# motor-control.net
KiCad netlist of a schematic drawn in EAGLE
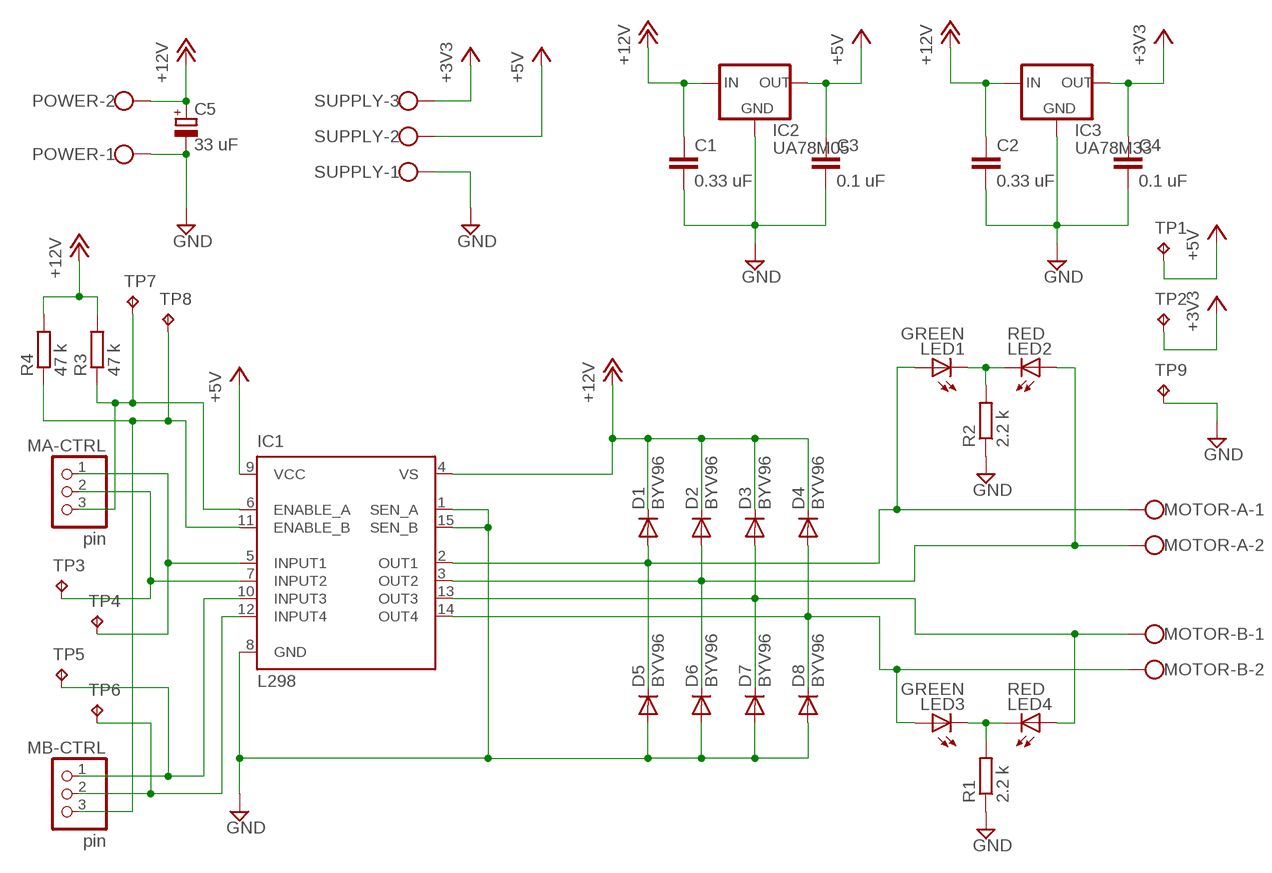
[diagram p0: schematic, sheet 1]

(export (version "E")
  (design (tool "Eeschema 10.0.6"))
  (components
    (comp (ref "C1")
      (value "0.33 uF")
      (footprint "eagle-import:C050-024X044")
      (libsource (lib "eagle-import") (part "C-EU050-024X044"))
    )
    (comp (ref "C2")
      (value "0.33 uF")
      (footprint "eagle-import:C050-024X044")
      (libsource (lib "eagle-import") (part "C-EU050-024X044"))
    )
    (comp (ref "C3")
      (value "0.1 uF")
      (footprint "eagle-import:C050-024X044")
      (libsource (lib "eagle-import") (part "C-EU050-024X044"))
    )
    (comp (ref "C4")
      (value "0.1 uF")
      (footprint "eagle-import:C050-024X044")
      (libsource (lib "eagle-import") (part "C-EU050-024X044"))
    )
    (comp (ref "C5")
      (value "33 uF")
      (footprint "eagle-import:E2,5-5")
      (libsource (lib "eagle-import") (part "CPOL-EUE2.5-5"))
    )
    (comp (ref "D1")
      (value "BYV96")
      (footprint "eagle-import:SOD57-10")
      (libsource (lib "eagle-import") (part "BYV96"))
    )
    (comp (ref "D2")
      (value "BYV96")
      (footprint "eagle-import:SOD57-10")
      (libsource (lib "eagle-import") (part "BYV96"))
    )
    (comp (ref "D3")
      (value "BYV96")
      (footprint "eagle-import:SOD57-10")
      (libsource (lib "eagle-import") (part "BYV96"))
    )
    (comp (ref "D4")
      (value "BYV96")
      (footprint "eagle-import:SOD57-10")
      (libsource (lib "eagle-import") (part "BYV96"))
    )
    (comp (ref "D5")
      (value "BYV96")
      (footprint "eagle-import:SOD57-10")
      (libsource (lib "eagle-import") (part "BYV96"))
    )
    (comp (ref "D6")
      (value "BYV96")
      (footprint "eagle-import:SOD57-10")
      (libsource (lib "eagle-import") (part "BYV96"))
    )
    (comp (ref "D7")
      (value "BYV96")
      (footprint "eagle-import:SOD57-10")
      (libsource (lib "eagle-import") (part "BYV96"))
    )
    (comp (ref "D8")
      (value "BYV96")
      (footprint "eagle-import:SOD57-10")
      (libsource (lib "eagle-import") (part "BYV96"))
    )
    (comp (ref "IC1")
      (value "L298")
      (footprint "eagle-import:MULTIWATT-15")
      (libsource (lib "eagle-import") (part "L298"))
    )
    (comp (ref "IC2")
      (value "UA78M05")
      (footprint "eagle-import:78XXS")
      (libsource (lib "eagle-import") (part "78XXS"))
    )
    (comp (ref "IC3")
      (value "UA78M33")
      (footprint "eagle-import:78XXS")
      (libsource (lib "eagle-import") (part "78XXS"))
    )
    (comp (ref "LED1")
      (value "GREEN")
      (footprint "eagle-import:LED5MM")
      (libsource (lib "eagle-import") (part "LED5MM"))
    )
    (comp (ref "LED2")
      (value "RED")
      (footprint "eagle-import:LED5MM")
      (libsource (lib "eagle-import") (part "LED5MM"))
    )
    (comp (ref "LED3")
      (value "GREEN")
      (footprint "eagle-import:LED5MM")
      (libsource (lib "eagle-import") (part "LED5MM"))
    )
    (comp (ref "LED4")
      (value "RED")
      (footprint "eagle-import:LED5MM")
      (libsource (lib "eagle-import") (part "LED5MM"))
    )
    (comp (ref "MA-CTRL")
      (value "pin")
      (footprint "eagle-import:1X03")
      (libsource (lib "eagle-import") (part "PINHD-1X3"))
    )
    (comp (ref "MB-CTRL")
      (value "pin")
      (footprint "eagle-import:1X03")
      (libsource (lib "eagle-import") (part "PINHD-1X3"))
    )
    (comp (ref "MOTOR-A")
      (value "W237-02P")
      (footprint "eagle-import:W237-132")
      (libsource (lib "eagle-import") (part "W237-02P"))
    )
    (comp (ref "MOTOR-B")
      (value "W237-02P")
      (footprint "eagle-import:W237-132")
      (libsource (lib "eagle-import") (part "W237-02P"))
    )
    (comp (ref "POWER")
      (value "W237-02P")
      (footprint "eagle-import:W237-132")
      (libsource (lib "eagle-import") (part "W237-02P"))
    )
    (comp (ref "R1")
      (value "2.2 k")
      (footprint "eagle-import:0207_7")
      (libsource (lib "eagle-import") (part "R-EU_0207/7"))
    )
    (comp (ref "R2")
      (value "2.2 k")
      (footprint "eagle-import:0207_7")
      (libsource (lib "eagle-import") (part "R-EU_0207/7"))
    )
    (comp (ref "R3")
      (value "47 k")
      (footprint "eagle-import:0207_7")
      (libsource (lib "eagle-import") (part "R-EU_0207/7"))
    )
    (comp (ref "R4")
      (value "47 k")
      (footprint "eagle-import:0207_7")
      (libsource (lib "eagle-import") (part "R-EU_0207/7"))
    )
    (comp (ref "SUPPLY")
      (value "W237-03P")
      (footprint "eagle-import:W237-133")
      (libsource (lib "eagle-import") (part "W237-03P"))
    )
    (comp (ref "TP1")
      (value "TPTP14SQ")
      (footprint "eagle-import:TP14SQ")
      (libsource (lib "eagle-import") (part "TPTP14SQ"))
    )
    (comp (ref "TP2")
      (value "TPTP14SQ")
      (footprint "eagle-import:TP14SQ")
      (libsource (lib "eagle-import") (part "TPTP14SQ"))
    )
    (comp (ref "TP3")
      (value "TPTP14SQ")
      (footprint "eagle-import:TP14SQ")
      (libsource (lib "eagle-import") (part "TPTP14SQ"))
    )
    (comp (ref "TP4")
      (value "TPTP14SQ")
      (footprint "eagle-import:TP14SQ")
      (libsource (lib "eagle-import") (part "TPTP14SQ"))
    )
    (comp (ref "TP5")
      (value "TPTP14SQ")
      (footprint "eagle-import:TP14SQ")
      (libsource (lib "eagle-import") (part "TPTP14SQ"))
    )
    (comp (ref "TP6")
      (value "TPTP14SQ")
      (footprint "eagle-import:TP14SQ")
      (libsource (lib "eagle-import") (part "TPTP14SQ"))
    )
    (comp (ref "TP7")
      (value "TPTP14SQ")
      (footprint "eagle-import:TP14SQ")
      (libsource (lib "eagle-import") (part "TPTP14SQ"))
    )
    (comp (ref "TP8")
      (value "TPTP14SQ")
      (footprint "eagle-import:TP14SQ")
      (libsource (lib "eagle-import") (part "TPTP14SQ"))
    )
    (comp (ref "TP9")
      (value "TPTP14SQ")
      (footprint "eagle-import:TP14SQ")
      (libsource (lib "eagle-import") (part "TPTP14SQ"))
    )
  )
  (nets
    (net (code "1") (name "+3V3") (class "Default")
      (node (ref "C4") (pin "1") (pinfunction "1_1") (pintype "passive"))
      (node (ref "IC3") (pin "OUT") (pinfunction "OUT_OUT") (pintype "passive"))
      (node (ref "SUPPLY") (pin "3") (pinfunction "KL_3") (pintype "passive"))
      (node (ref "TP2") (pin "TP") (pinfunction "TP_TP") (pintype "input"))
    )
    (net (code "2") (name "+5V") (class "Default")
      (node (ref "C3") (pin "1") (pinfunction "1_1") (pintype "passive"))
      (node (ref "IC1") (pin "9") (pinfunction "VCC_9") (pintype "power_in"))
      (node (ref "IC2") (pin "OUT") (pinfunction "OUT_OUT") (pintype "passive"))
      (node (ref "SUPPLY") (pin "2") (pinfunction "KL_2") (pintype "passive"))
      (node (ref "TP1") (pin "TP") (pinfunction "TP_TP") (pintype "input"))
    )
    (net (code "3") (name "+12V") (class "Default")
      (node (ref "C1") (pin "1") (pinfunction "1_1") (pintype "passive"))
      (node (ref "C2") (pin "1") (pinfunction "1_1") (pintype "passive"))
      (node (ref "C5") (pin "+") (pinfunction "+_+") (pintype "passive"))
      (node (ref "D1") (pin "C") (pinfunction "C_C") (pintype "passive"))
      (node (ref "D2") (pin "C") (pinfunction "C_C") (pintype "passive"))
      (node (ref "D3") (pin "C") (pinfunction "C_C") (pintype "passive"))
      (node (ref "D4") (pin "C") (pinfunction "C_C") (pintype "passive"))
      (node (ref "IC1") (pin "4") (pinfunction "VS_4") (pintype "power_in"))
      (node (ref "IC2") (pin "IN") (pinfunction "IN_IN") (pintype "input"))
      (node (ref "IC3") (pin "IN") (pinfunction "IN_IN") (pintype "input"))
      (node (ref "POWER") (pin "2") (pinfunction "KL_2") (pintype "passive"))
      (node (ref "R3") (pin "2") (pinfunction "2_2") (pintype "passive"))
      (node (ref "R4") (pin "2") (pinfunction "2_2") (pintype "passive"))
    )
    (net (code "4") (name "GND") (class "Default")
      (node (ref "C1") (pin "2") (pinfunction "2_2") (pintype "passive"))
      (node (ref "C2") (pin "2") (pinfunction "2_2") (pintype "passive"))
      (node (ref "C3") (pin "2") (pinfunction "2_2") (pintype "passive"))
      (node (ref "C4") (pin "2") (pinfunction "2_2") (pintype "passive"))
      (node (ref "C5") (pin "-") (pinfunction "-_-") (pintype "passive"))
      (node (ref "D5") (pin "A") (pinfunction "A_A") (pintype "passive"))
      (node (ref "D6") (pin "A") (pinfunction "A_A") (pintype "passive"))
      (node (ref "D7") (pin "A") (pinfunction "A_A") (pintype "passive"))
      (node (ref "D8") (pin "A") (pinfunction "A_A") (pintype "passive"))
      (node (ref "IC1") (pin "1") (pinfunction "SEN_A_1") (pintype "input"))
      (node (ref "IC1") (pin "15") (pinfunction "SEN_B_15") (pintype "input"))
      (node (ref "IC1") (pin "8") (pinfunction "GND_8") (pintype "power_in"))
      (node (ref "IC2") (pin "GND") (pinfunction "GND_GND") (pintype "input"))
      (node (ref "IC3") (pin "GND") (pinfunction "GND_GND") (pintype "input"))
      (node (ref "POWER") (pin "1") (pinfunction "KL_1") (pintype "passive"))
      (node (ref "R1") (pin "1") (pinfunction "1_1") (pintype "passive"))
      (node (ref "R2") (pin "1") (pinfunction "1_1") (pintype "passive"))
      (node (ref "SUPPLY") (pin "1") (pinfunction "KL_1") (pintype "passive"))
      (node (ref "TP9") (pin "TP") (pinfunction "TP_TP") (pintype "input"))
    )
    (net (code "5") (name "Net-(IC1-ENABLE_A)") (class "Default")
      (node (ref "IC1") (pin "6") (pinfunction "ENABLE_A_6") (pintype "input"))
      (node (ref "MA-CTRL") (pin "3") (pinfunction "3_3") (pintype "passive"))
      (node (ref "R3") (pin "1") (pinfunction "1_1") (pintype "passive"))
      (node (ref "TP7") (pin "TP") (pinfunction "TP_TP") (pintype "input"))
    )
    (net (code "6") (name "Net-(IC1-ENABLE_B)") (class "Default")
      (node (ref "IC1") (pin "11") (pinfunction "ENABLE_B_11") (pintype "input"))
      (node (ref "MB-CTRL") (pin "3") (pinfunction "3_3") (pintype "passive"))
      (node (ref "R4") (pin "1") (pinfunction "1_1") (pintype "passive"))
      (node (ref "TP8") (pin "TP") (pinfunction "TP_TP") (pintype "input"))
    )
    (net (code "7") (name "Net-(IC1-INPUT1)") (class "Default")
      (node (ref "IC1") (pin "5") (pinfunction "INPUT1_5") (pintype "input"))
      (node (ref "MA-CTRL") (pin "1") (pinfunction "1_1") (pintype "passive"))
      (node (ref "TP4") (pin "TP") (pinfunction "TP_TP") (pintype "input"))
    )
    (net (code "8") (name "Net-(IC1-INPUT2)") (class "Default")
      (node (ref "IC1") (pin "7") (pinfunction "INPUT2_7") (pintype "input"))
      (node (ref "MA-CTRL") (pin "2") (pinfunction "2_2") (pintype "passive"))
      (node (ref "TP3") (pin "TP") (pinfunction "TP_TP") (pintype "input"))
    )
    (net (code "9") (name "Net-(IC1-INPUT3)") (class "Default")
      (node (ref "IC1") (pin "10") (pinfunction "INPUT3_10") (pintype "input"))
      (node (ref "MB-CTRL") (pin "1") (pinfunction "1_1") (pintype "passive"))
      (node (ref "TP5") (pin "TP") (pinfunction "TP_TP") (pintype "input"))
    )
    (net (code "10") (name "Net-(IC1-INPUT4)") (class "Default")
      (node (ref "IC1") (pin "12") (pinfunction "INPUT4_12") (pintype "input"))
      (node (ref "MB-CTRL") (pin "2") (pinfunction "2_2") (pintype "passive"))
      (node (ref "TP6") (pin "TP") (pinfunction "TP_TP") (pintype "input"))
    )
    (net (code "11") (name "Net-(IC1-OUT1)") (class "Default")
      (node (ref "D1") (pin "A") (pinfunction "A_A") (pintype "passive"))
      (node (ref "D5") (pin "C") (pinfunction "C_C") (pintype "passive"))
      (node (ref "IC1") (pin "2") (pinfunction "OUT1_2") (pintype "output"))
      (node (ref "LED1") (pin "A") (pinfunction "A_A") (pintype "passive"))
      (node (ref "MOTOR-A") (pin "1") (pinfunction "KL_1") (pintype "passive"))
    )
    (net (code "12") (name "Net-(IC1-OUT2)") (class "Default")
      (node (ref "D2") (pin "A") (pinfunction "A_A") (pintype "passive"))
      (node (ref "D6") (pin "C") (pinfunction "C_C") (pintype "passive"))
      (node (ref "IC1") (pin "3") (pinfunction "OUT2_3") (pintype "output"))
      (node (ref "LED2") (pin "A") (pinfunction "A_A") (pintype "passive"))
      (node (ref "MOTOR-A") (pin "2") (pinfunction "KL_2") (pintype "passive"))
    )
    (net (code "13") (name "Net-(IC1-OUT3)") (class "Default")
      (node (ref "D3") (pin "A") (pinfunction "A_A") (pintype "passive"))
      (node (ref "D7") (pin "C") (pinfunction "C_C") (pintype "passive"))
      (node (ref "IC1") (pin "13") (pinfunction "OUT3_13") (pintype "output"))
      (node (ref "LED4") (pin "A") (pinfunction "A_A") (pintype "passive"))
      (node (ref "MOTOR-B") (pin "1") (pinfunction "KL_1") (pintype "passive"))
    )
    (net (code "14") (name "Net-(IC1-OUT4)") (class "Default")
      (node (ref "D4") (pin "A") (pinfunction "A_A") (pintype "passive"))
      (node (ref "D8") (pin "C") (pinfunction "C_C") (pintype "passive"))
      (node (ref "IC1") (pin "14") (pinfunction "OUT4_14") (pintype "output"))
      (node (ref "LED3") (pin "A") (pinfunction "A_A") (pintype "passive"))
      (node (ref "MOTOR-B") (pin "2") (pinfunction "KL_2") (pintype "passive"))
    )
    (net (code "15") (name "Net-(LED1-C)") (class "Default")
      (node (ref "LED1") (pin "K") (pinfunction "C_K") (pintype "passive"))
      (node (ref "LED2") (pin "K") (pinfunction "C_K") (pintype "passive"))
      (node (ref "R2") (pin "2") (pinfunction "2_2") (pintype "passive"))
    )
    (net (code "16") (name "Net-(LED3-C)") (class "Default")
      (node (ref "LED3") (pin "K") (pinfunction "C_K") (pintype "passive"))
      (node (ref "LED4") (pin "K") (pinfunction "C_K") (pintype "passive"))
      (node (ref "R1") (pin "2") (pinfunction "2_2") (pintype "passive"))
    )
  )
)
